# intercon.net
KiCad netlist of a schematic drawn in EAGLE
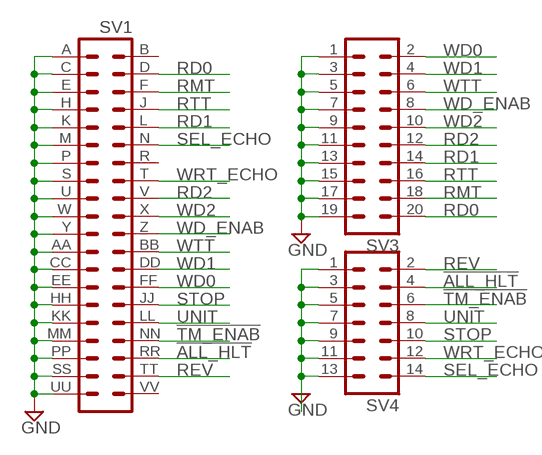
[diagram p0: schematic, sheet 1]

(export (version "E")
  (design (tool "Eeschema 10.0.6"))
  (components
    (comp (ref "SV1")
      (value "DEC40PINV")
      (footprint "eagle-import:DEC40PINV")
      (libsource (lib "eagle-import") (part "DEC40PINV"))
    )
    (comp (ref "SV3")
      (value "MA10-2")
      (footprint "eagle-import:MA10-2")
      (libsource (lib "eagle-import") (part "MA10-2"))
    )
    (comp (ref "SV4")
      (value "MA07-2")
      (footprint "eagle-import:MA07-2")
      (libsource (lib "eagle-import") (part "MA07-2"))
    )
  )
  (nets
    (net (code "1") (name "/RD0") (class "Default")
      (node (ref "SV1") (pin "D") (pinfunction "4_D") (pintype "bidirectional"))
      (node (ref "SV3") (pin "20") (pinfunction "20_20") (pintype "passive"))
    )
    (net (code "2") (name "/RD1") (class "Default")
      (node (ref "SV1") (pin "L") (pinfunction "10_L") (pintype "bidirectional"))
      (node (ref "SV3") (pin "14") (pinfunction "14_14") (pintype "passive"))
    )
    (net (code "3") (name "/RD2") (class "Default")
      (node (ref "SV1") (pin "V") (pinfunction "18_V") (pintype "bidirectional"))
      (node (ref "SV3") (pin "12") (pinfunction "12_12") (pintype "passive"))
    )
    (net (code "4") (name "/REV") (class "Default")
      (node (ref "SV1") (pin "TT") (pinfunction "38_TT") (pintype "bidirectional"))
      (node (ref "SV4") (pin "2") (pinfunction "2_2") (pintype "passive"))
    )
    (net (code "5") (name "/RMT") (class "Default")
      (node (ref "SV1") (pin "F") (pinfunction "6_F") (pintype "bidirectional"))
      (node (ref "SV3") (pin "18") (pinfunction "18_18") (pintype "passive"))
    )
    (net (code "6") (name "/RTT") (class "Default")
      (node (ref "SV1") (pin "J") (pinfunction "8_J") (pintype "bidirectional"))
      (node (ref "SV3") (pin "16") (pinfunction "16_16") (pintype "passive"))
    )
    (net (code "7") (name "/SEL_ECHO") (class "Default")
      (node (ref "SV1") (pin "N") (pinfunction "12_N") (pintype "bidirectional"))
      (node (ref "SV4") (pin "14") (pinfunction "14_14") (pintype "passive"))
    )
    (net (code "8") (name "/STOP") (class "Default")
      (node (ref "SV1") (pin "JJ") (pinfunction "30_JJ") (pintype "bidirectional"))
      (node (ref "SV4") (pin "10") (pinfunction "10_10") (pintype "passive"))
    )
    (net (code "9") (name "/UNIT") (class "Default")
      (node (ref "SV1") (pin "LL") (pinfunction "32_LL") (pintype "bidirectional"))
      (node (ref "SV4") (pin "8") (pinfunction "8_8") (pintype "passive"))
    )
    (net (code "10") (name "/WD0") (class "Default")
      (node (ref "SV1") (pin "FF") (pinfunction "28_FF") (pintype "bidirectional"))
      (node (ref "SV3") (pin "2") (pinfunction "2_2") (pintype "passive"))
    )
    (net (code "11") (name "/WD1") (class "Default")
      (node (ref "SV1") (pin "DD") (pinfunction "26_DD") (pintype "bidirectional"))
      (node (ref "SV3") (pin "4") (pinfunction "4_4") (pintype "passive"))
    )
    (net (code "12") (name "/WD2") (class "Default")
      (node (ref "SV1") (pin "X") (pinfunction "20_X") (pintype "bidirectional"))
      (node (ref "SV3") (pin "10") (pinfunction "10_10") (pintype "passive"))
    )
    (net (code "13") (name "/WD_ENAB") (class "Default")
      (node (ref "SV1") (pin "Z") (pinfunction "22_Z") (pintype "bidirectional"))
      (node (ref "SV3") (pin "8") (pinfunction "8_8") (pintype "passive"))
    )
    (net (code "14") (name "/WRT_ECHO") (class "Default")
      (node (ref "SV1") (pin "T") (pinfunction "16_T") (pintype "bidirectional"))
      (node (ref "SV4") (pin "12") (pinfunction "12_12") (pintype "passive"))
    )
    (net (code "15") (name "/WTT") (class "Default")
      (node (ref "SV1") (pin "BB") (pinfunction "24_BB") (pintype "bidirectional"))
      (node (ref "SV3") (pin "6") (pinfunction "6_6") (pintype "passive"))
    )
    (net (code "16") (name "/~{ALL_HLT}") (class "Default")
      (node (ref "SV1") (pin "RR") (pinfunction "36_RR") (pintype "bidirectional"))
      (node (ref "SV4") (pin "4") (pinfunction "4_4") (pintype "passive"))
    )
    (net (code "17") (name "/~{TM_ENAB}") (class "Default")
      (node (ref "SV1") (pin "NN") (pinfunction "34_NN") (pintype "bidirectional"))
      (node (ref "SV4") (pin "6") (pinfunction "6_6") (pintype "passive"))
    )
    (net (code "18") (name "GND") (class "Default")
      (node (ref "SV1") (pin "A") (pinfunction "1_A") (pintype "bidirectional"))
      (node (ref "SV1") (pin "AA") (pinfunction "23_AA") (pintype "bidirectional"))
      (node (ref "SV1") (pin "C") (pinfunction "3_C") (pintype "bidirectional"))
      (node (ref "SV1") (pin "CC") (pinfunction "25_CC") (pintype "bidirectional"))
      (node (ref "SV1") (pin "E") (pinfunction "5_E") (pintype "bidirectional"))
      (node (ref "SV1") (pin "EE") (pinfunction "27_EE") (pintype "bidirectional"))
      (node (ref "SV1") (pin "H") (pinfunction "7_H") (pintype "bidirectional"))
      (node (ref "SV1") (pin "HH") (pinfunction "29_HH") (pintype "bidirectional"))
      (node (ref "SV1") (pin "K") (pinfunction "9_K") (pintype "bidirectional"))
      (node (ref "SV1") (pin "KK") (pinfunction "31_KK") (pintype "bidirectional"))
      (node (ref "SV1") (pin "M") (pinfunction "11_M") (pintype "bidirectional"))
      (node (ref "SV1") (pin "MM") (pinfunction "33_MM") (pintype "bidirectional"))
      (node (ref "SV1") (pin "P") (pinfunction "13_P") (pintype "bidirectional"))
      (node (ref "SV1") (pin "PP") (pinfunction "35_PP") (pintype "bidirectional"))
      (node (ref "SV1") (pin "S") (pinfunction "15_S") (pintype "bidirectional"))
      (node (ref "SV1") (pin "SS") (pinfunction "37_SS") (pintype "bidirectional"))
      (node (ref "SV1") (pin "U") (pinfunction "17_U") (pintype "bidirectional"))
      (node (ref "SV1") (pin "UU") (pinfunction "39_UU") (pintype "bidirectional"))
      (node (ref "SV1") (pin "W") (pinfunction "19_W") (pintype "bidirectional"))
      (node (ref "SV1") (pin "Y") (pinfunction "21_Y") (pintype "bidirectional"))
      (node (ref "SV3") (pin "1") (pinfunction "1_1") (pintype "passive"))
      (node (ref "SV3") (pin "11") (pinfunction "11_11") (pintype "passive"))
      (node (ref "SV3") (pin "13") (pinfunction "13_13") (pintype "passive"))
      (node (ref "SV3") (pin "15") (pinfunction "15_15") (pintype "passive"))
      (node (ref "SV3") (pin "17") (pinfunction "17_17") (pintype "passive"))
      (node (ref "SV3") (pin "19") (pinfunction "19_19") (pintype "passive"))
      (node (ref "SV3") (pin "3") (pinfunction "3_3") (pintype "passive"))
      (node (ref "SV3") (pin "5") (pinfunction "5_5") (pintype "passive"))
      (node (ref "SV3") (pin "7") (pinfunction "7_7") (pintype "passive"))
      (node (ref "SV3") (pin "9") (pinfunction "9_9") (pintype "passive"))
      (node (ref "SV4") (pin "1") (pinfunction "1_1") (pintype "passive"))
      (node (ref "SV4") (pin "11") (pinfunction "11_11") (pintype "passive"))
      (node (ref "SV4") (pin "13") (pinfunction "13_13") (pintype "passive"))
      (node (ref "SV4") (pin "3") (pinfunction "3_3") (pintype "passive"))
      (node (ref "SV4") (pin "5") (pinfunction "5_5") (pintype "passive"))
      (node (ref "SV4") (pin "7") (pinfunction "7_7") (pintype "passive"))
      (node (ref "SV4") (pin "9") (pinfunction "9_9") (pintype "passive"))
    )
    (net (code "19") (name "unconnected-(SV1-2-PadB)") (class "Default")
      (node (ref "SV1") (pin "B") (pinfunction "2_B") (pintype "bidirectional"))
    )
    (net (code "20") (name "unconnected-(SV1-14-PadR)") (class "Default")
      (node (ref "SV1") (pin "R") (pinfunction "14_R") (pintype "bidirectional"))
    )
    (net (code "21") (name "unconnected-(SV1-40-PadVV)") (class "Default")
      (node (ref "SV1") (pin "VV") (pinfunction "40_VV") (pintype "bidirectional"))
    )
  )
)
